# 2023-08-05_LVMi_Thermistors.net
KiCad netlist of a schematic drawn in EAGLE
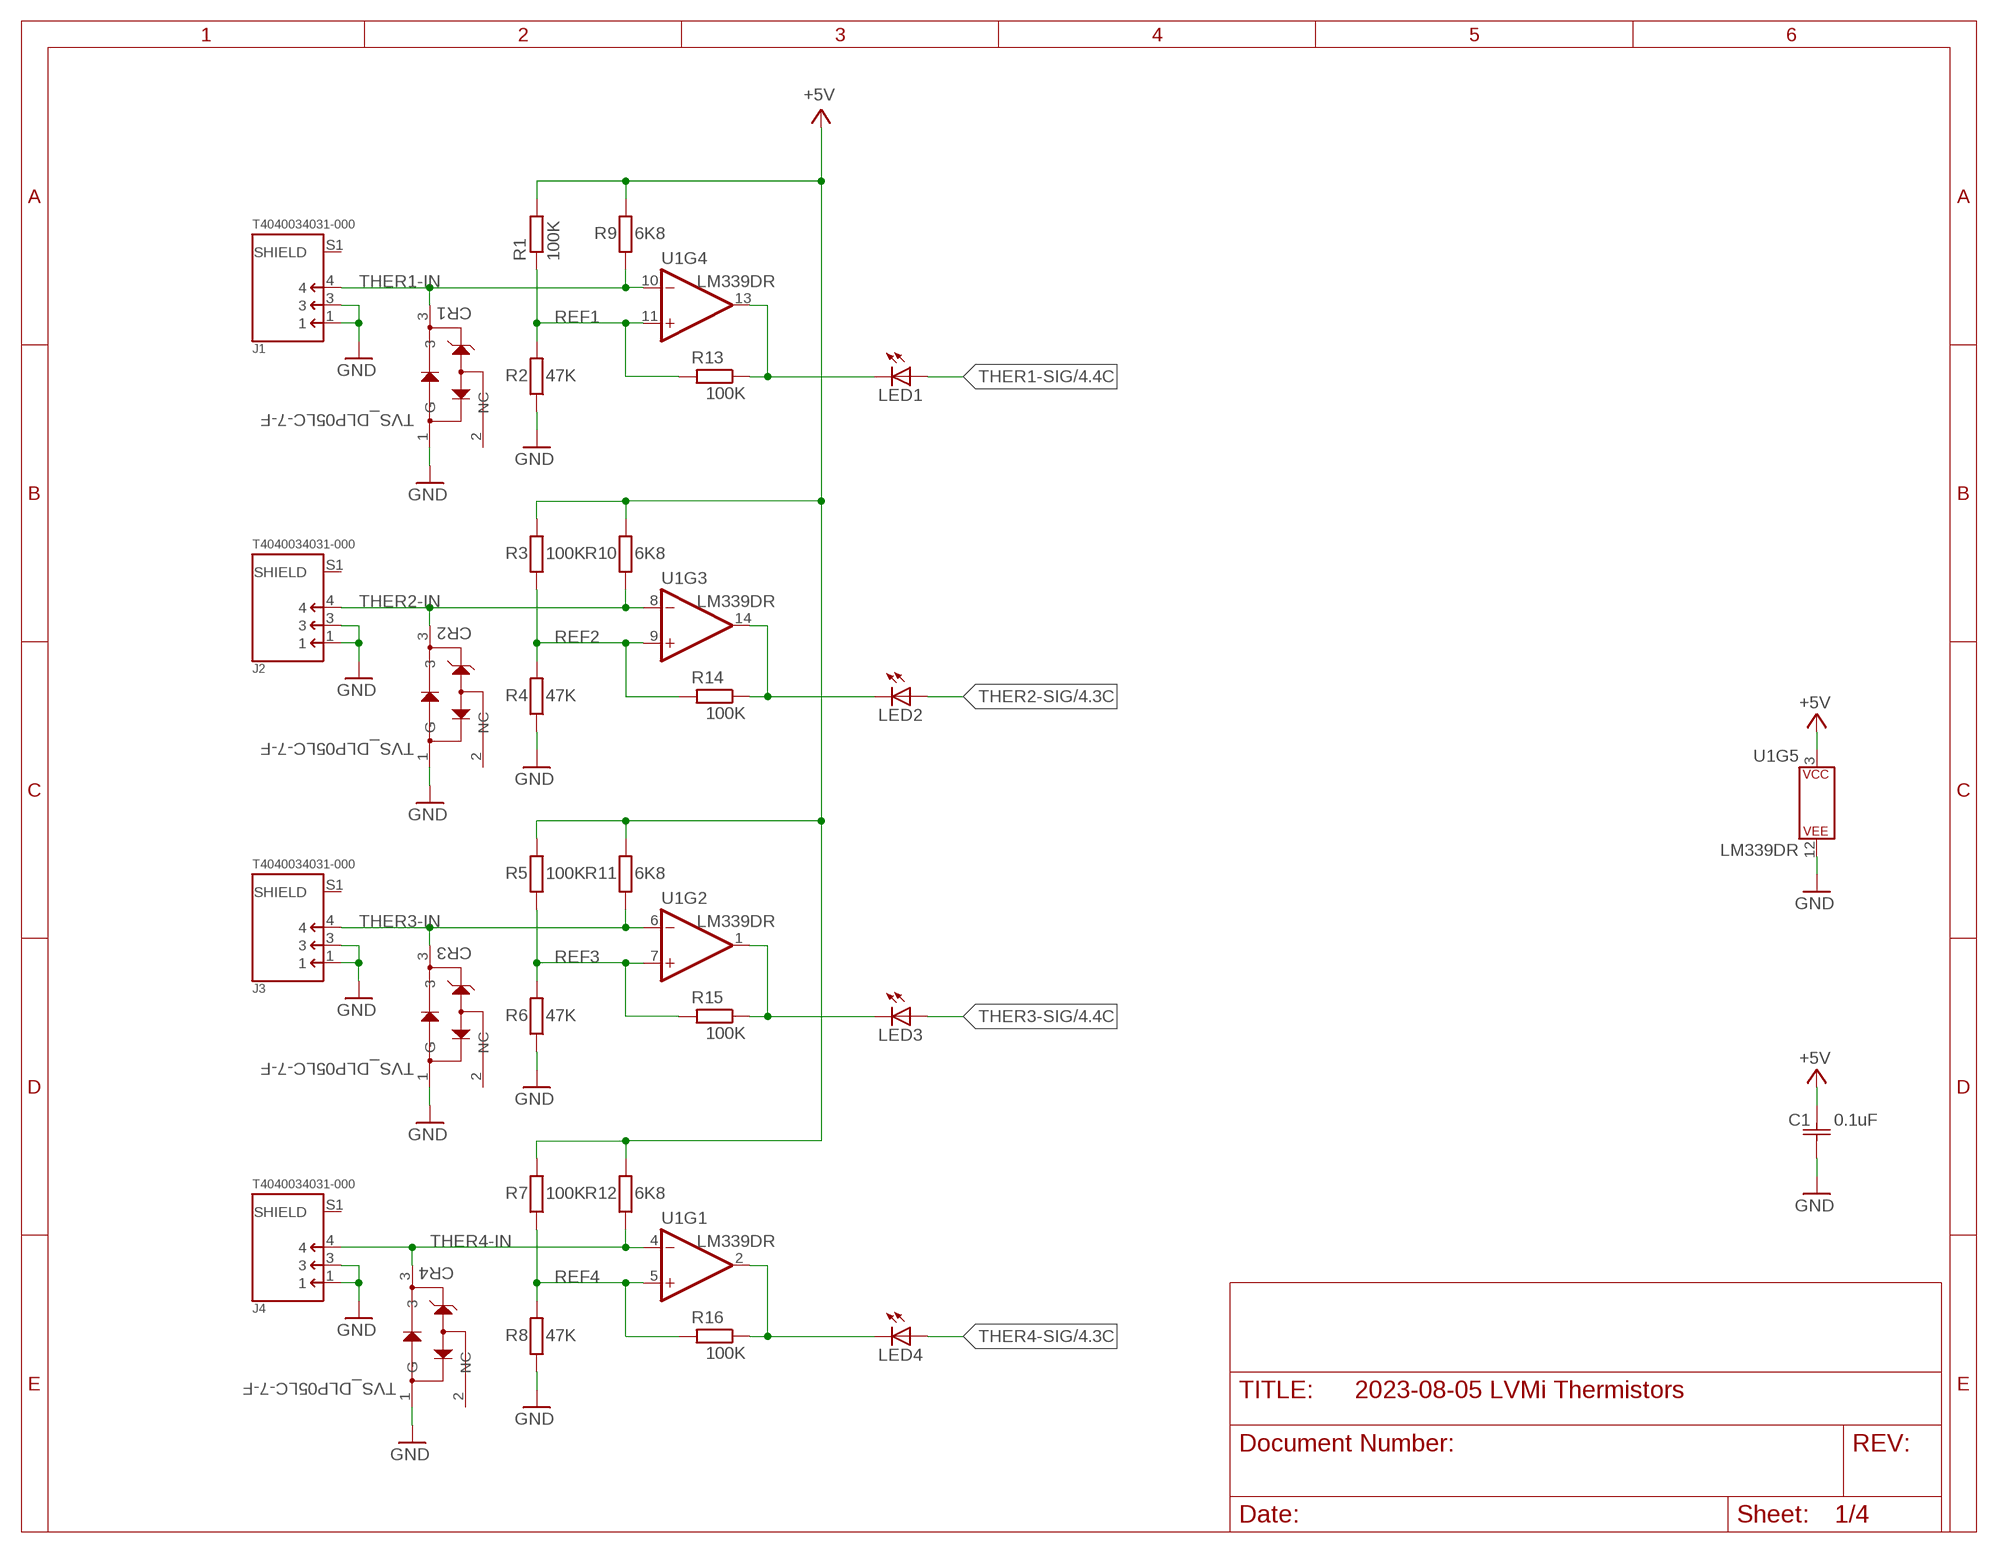
[diagram p0: schematic, sheet 1]
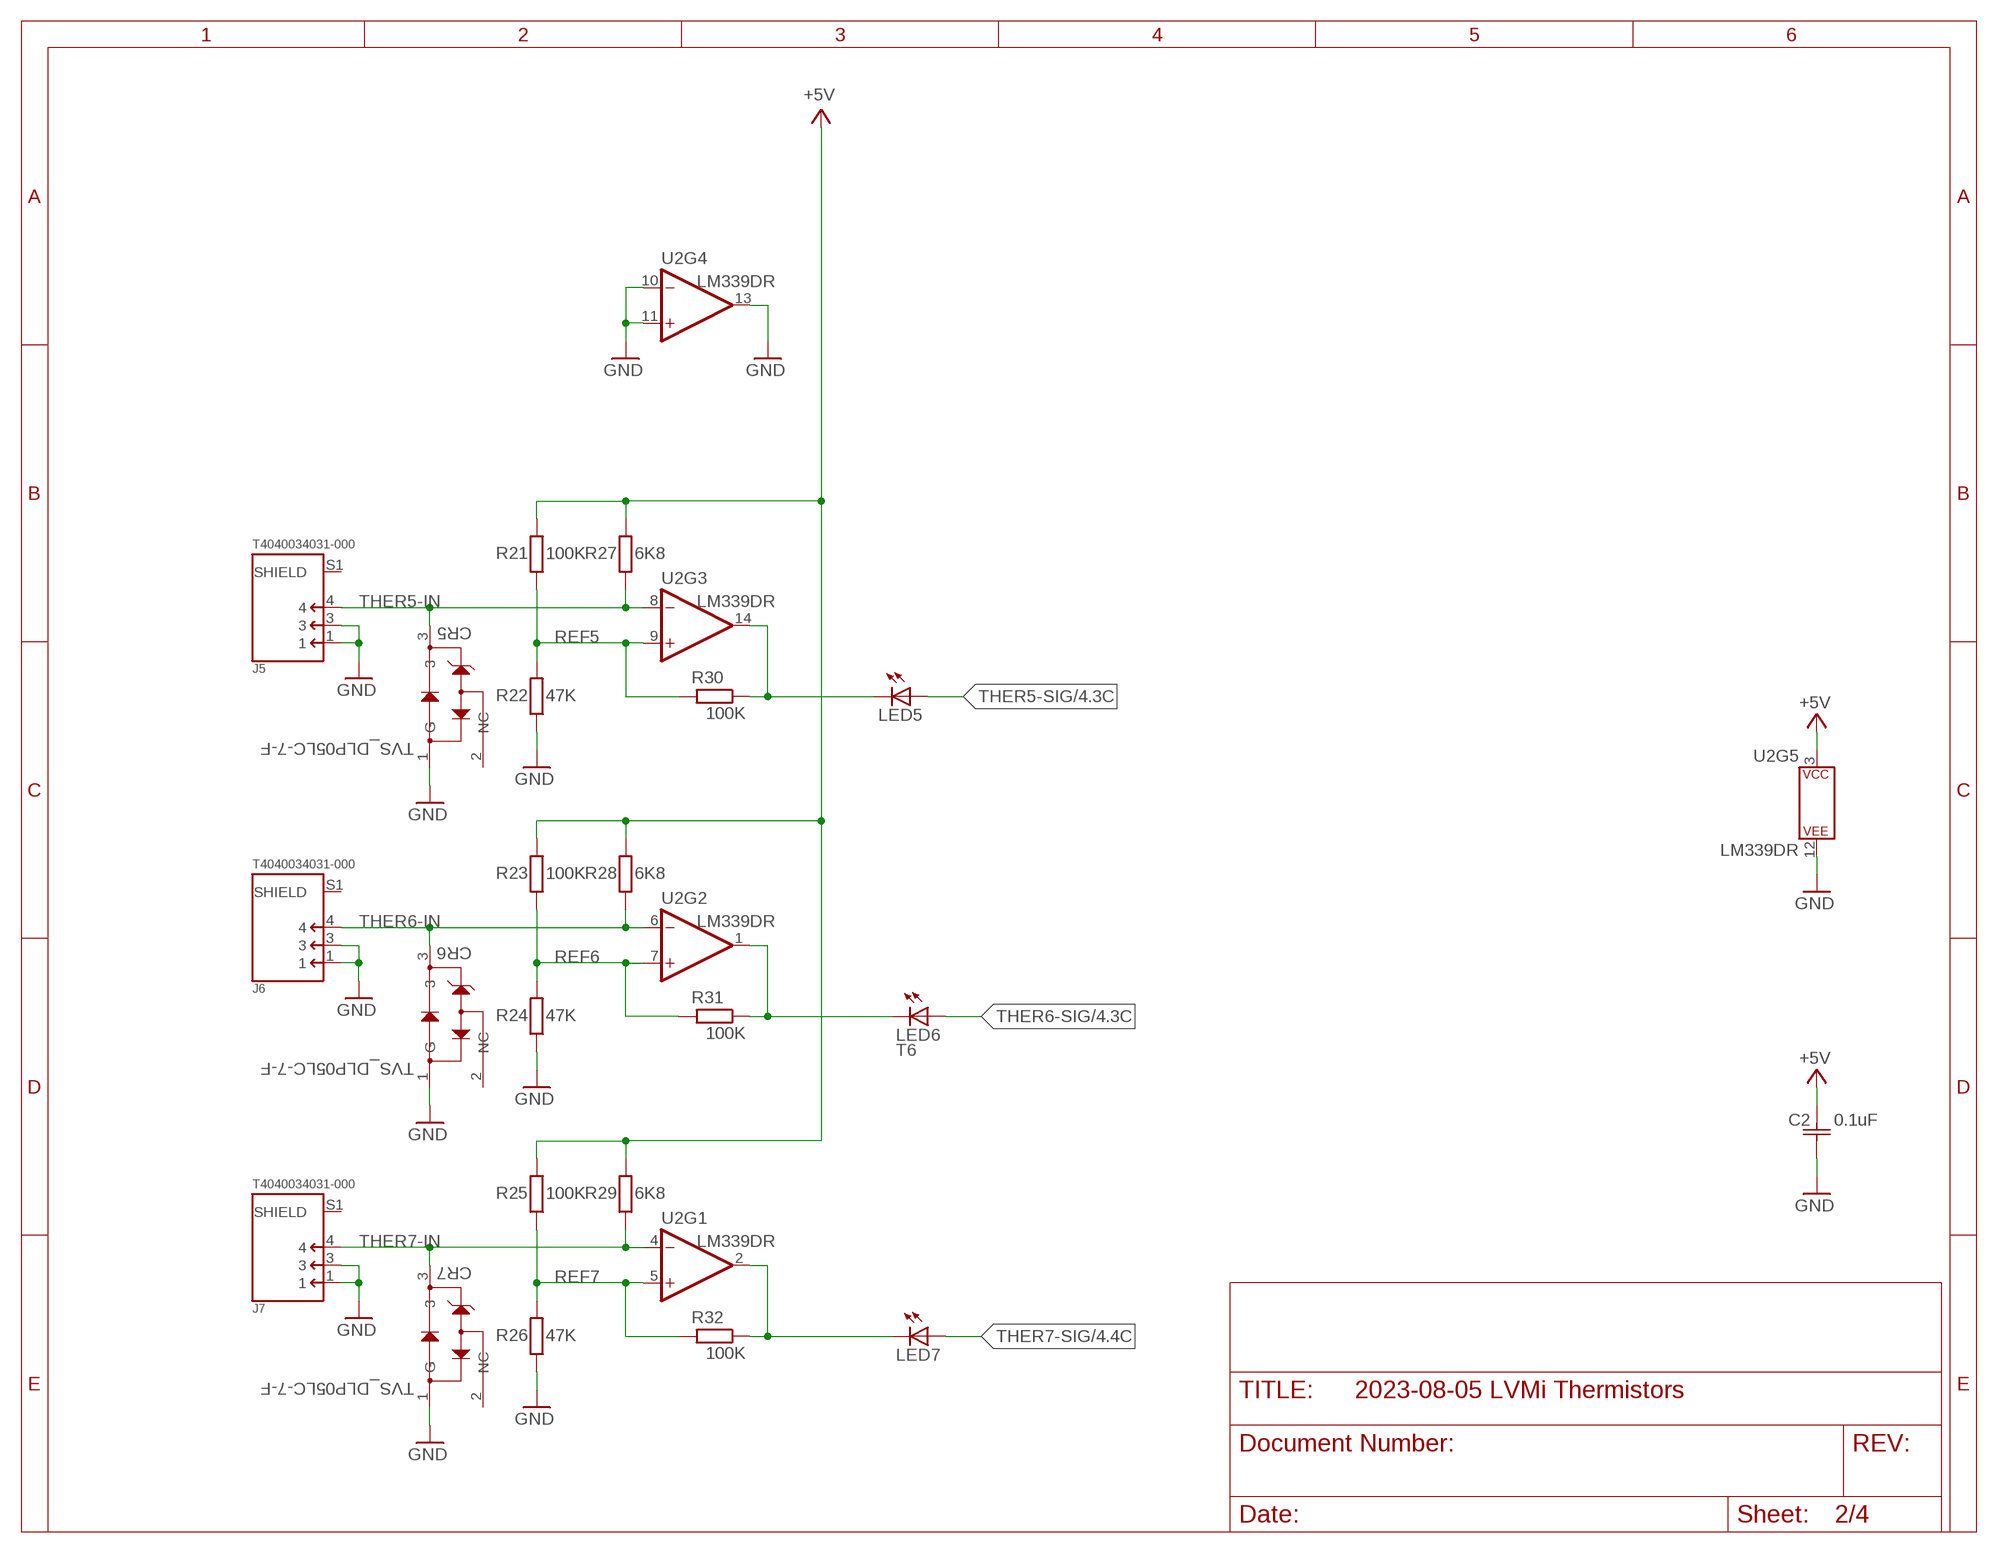
[diagram p1: schematic, sheet 2]
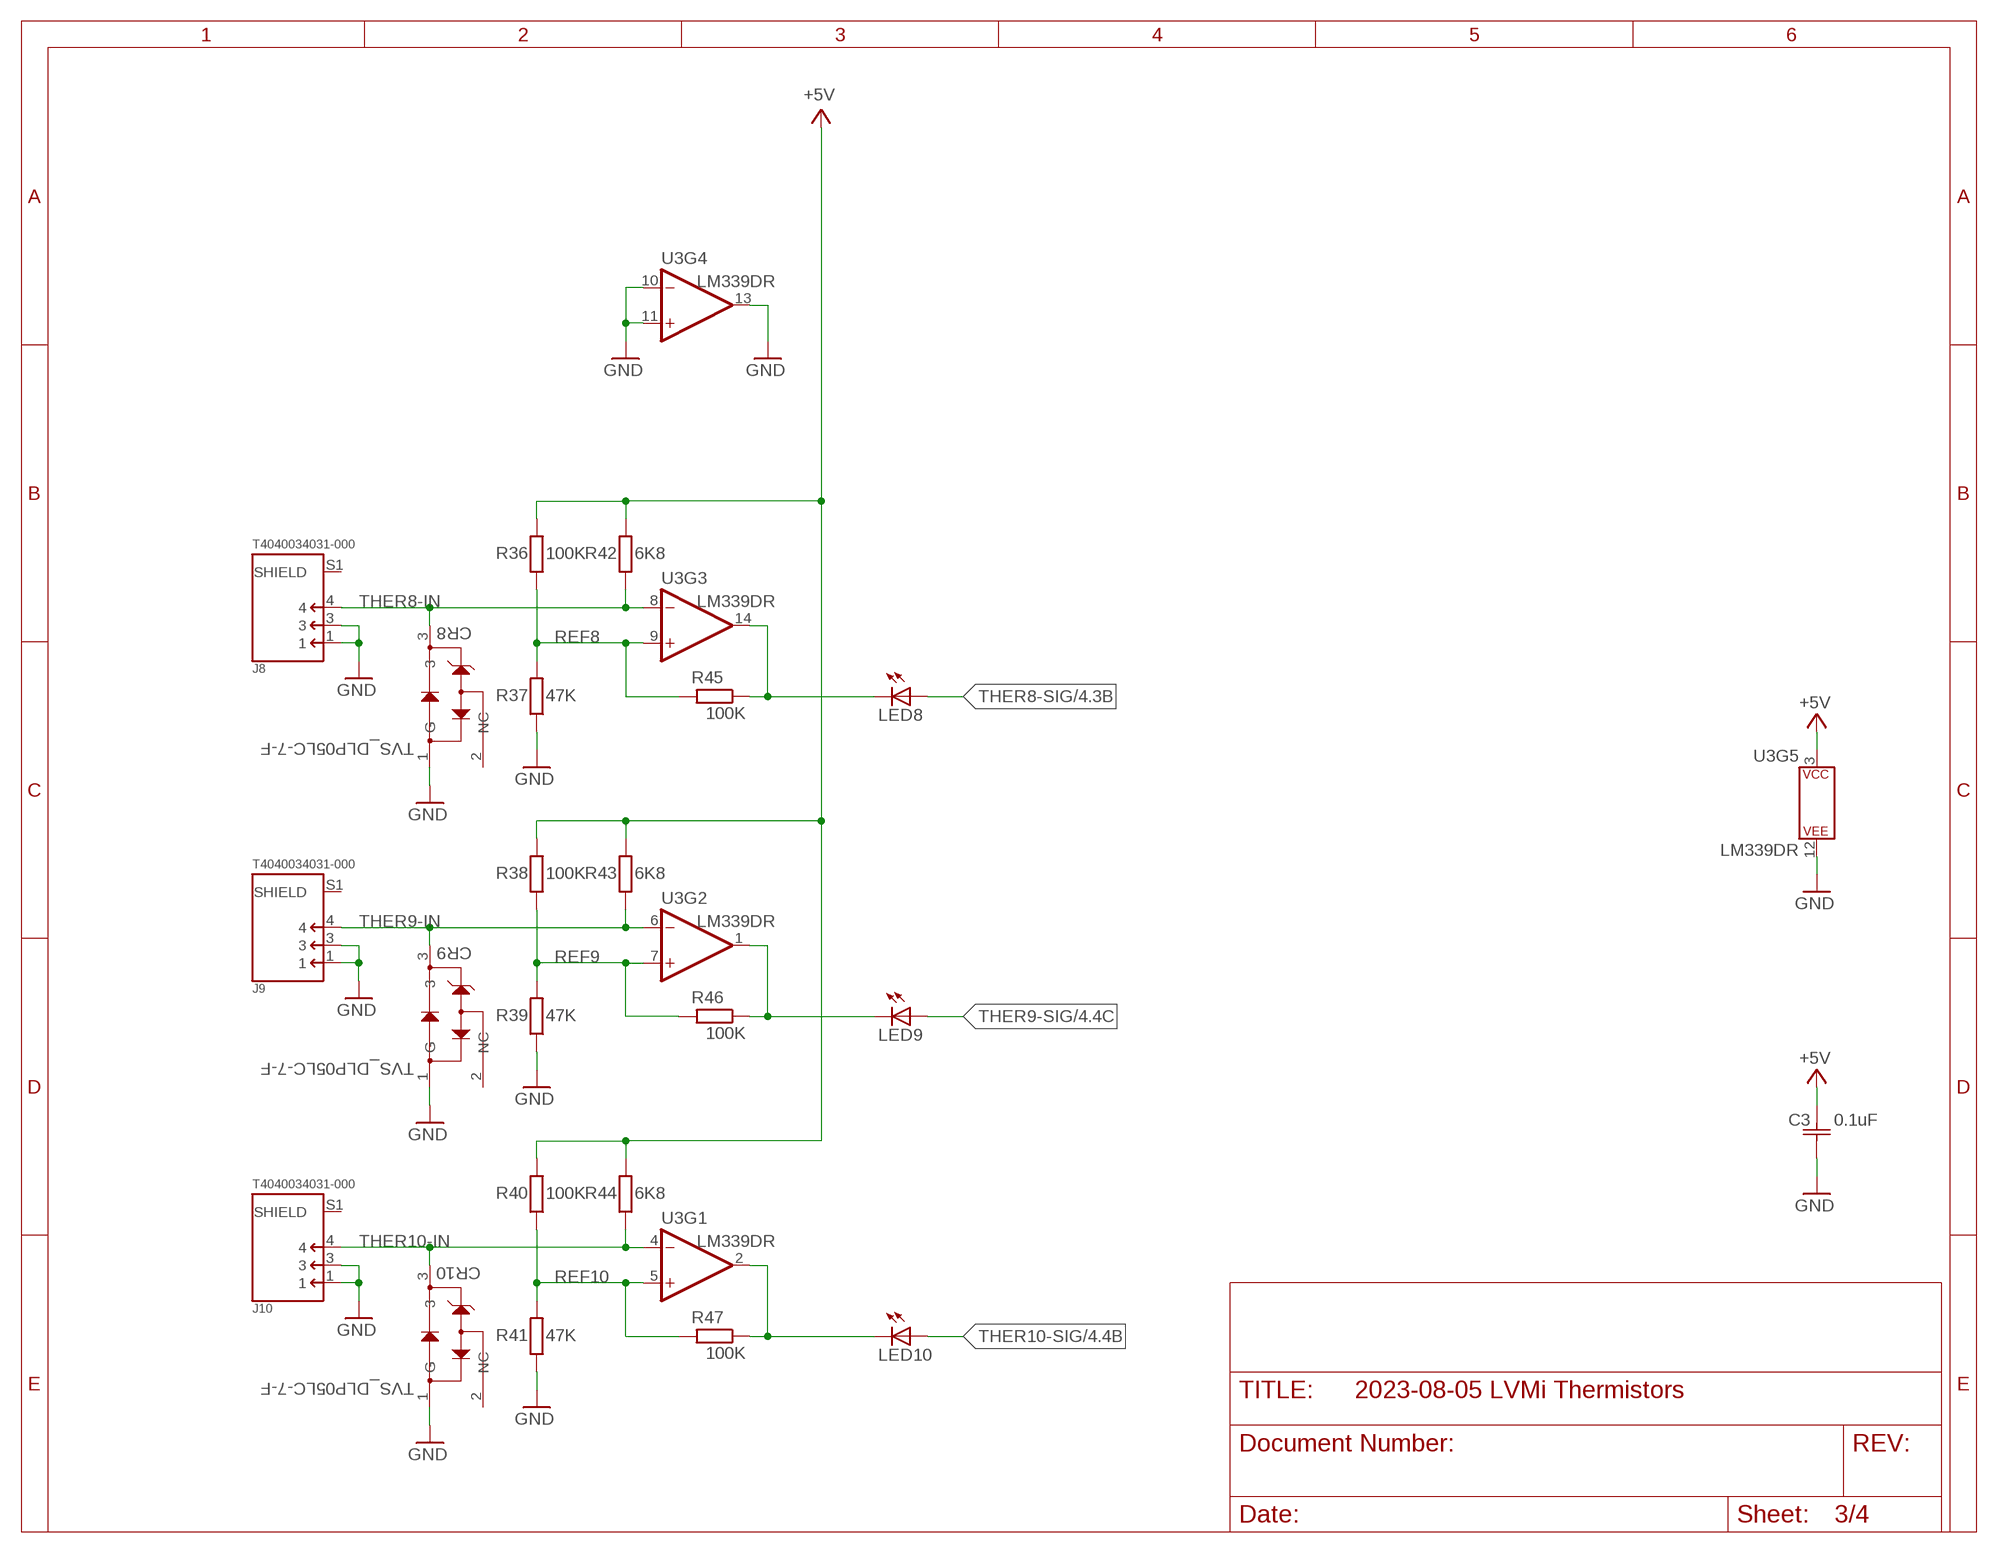
[diagram p2: schematic, sheet 3]
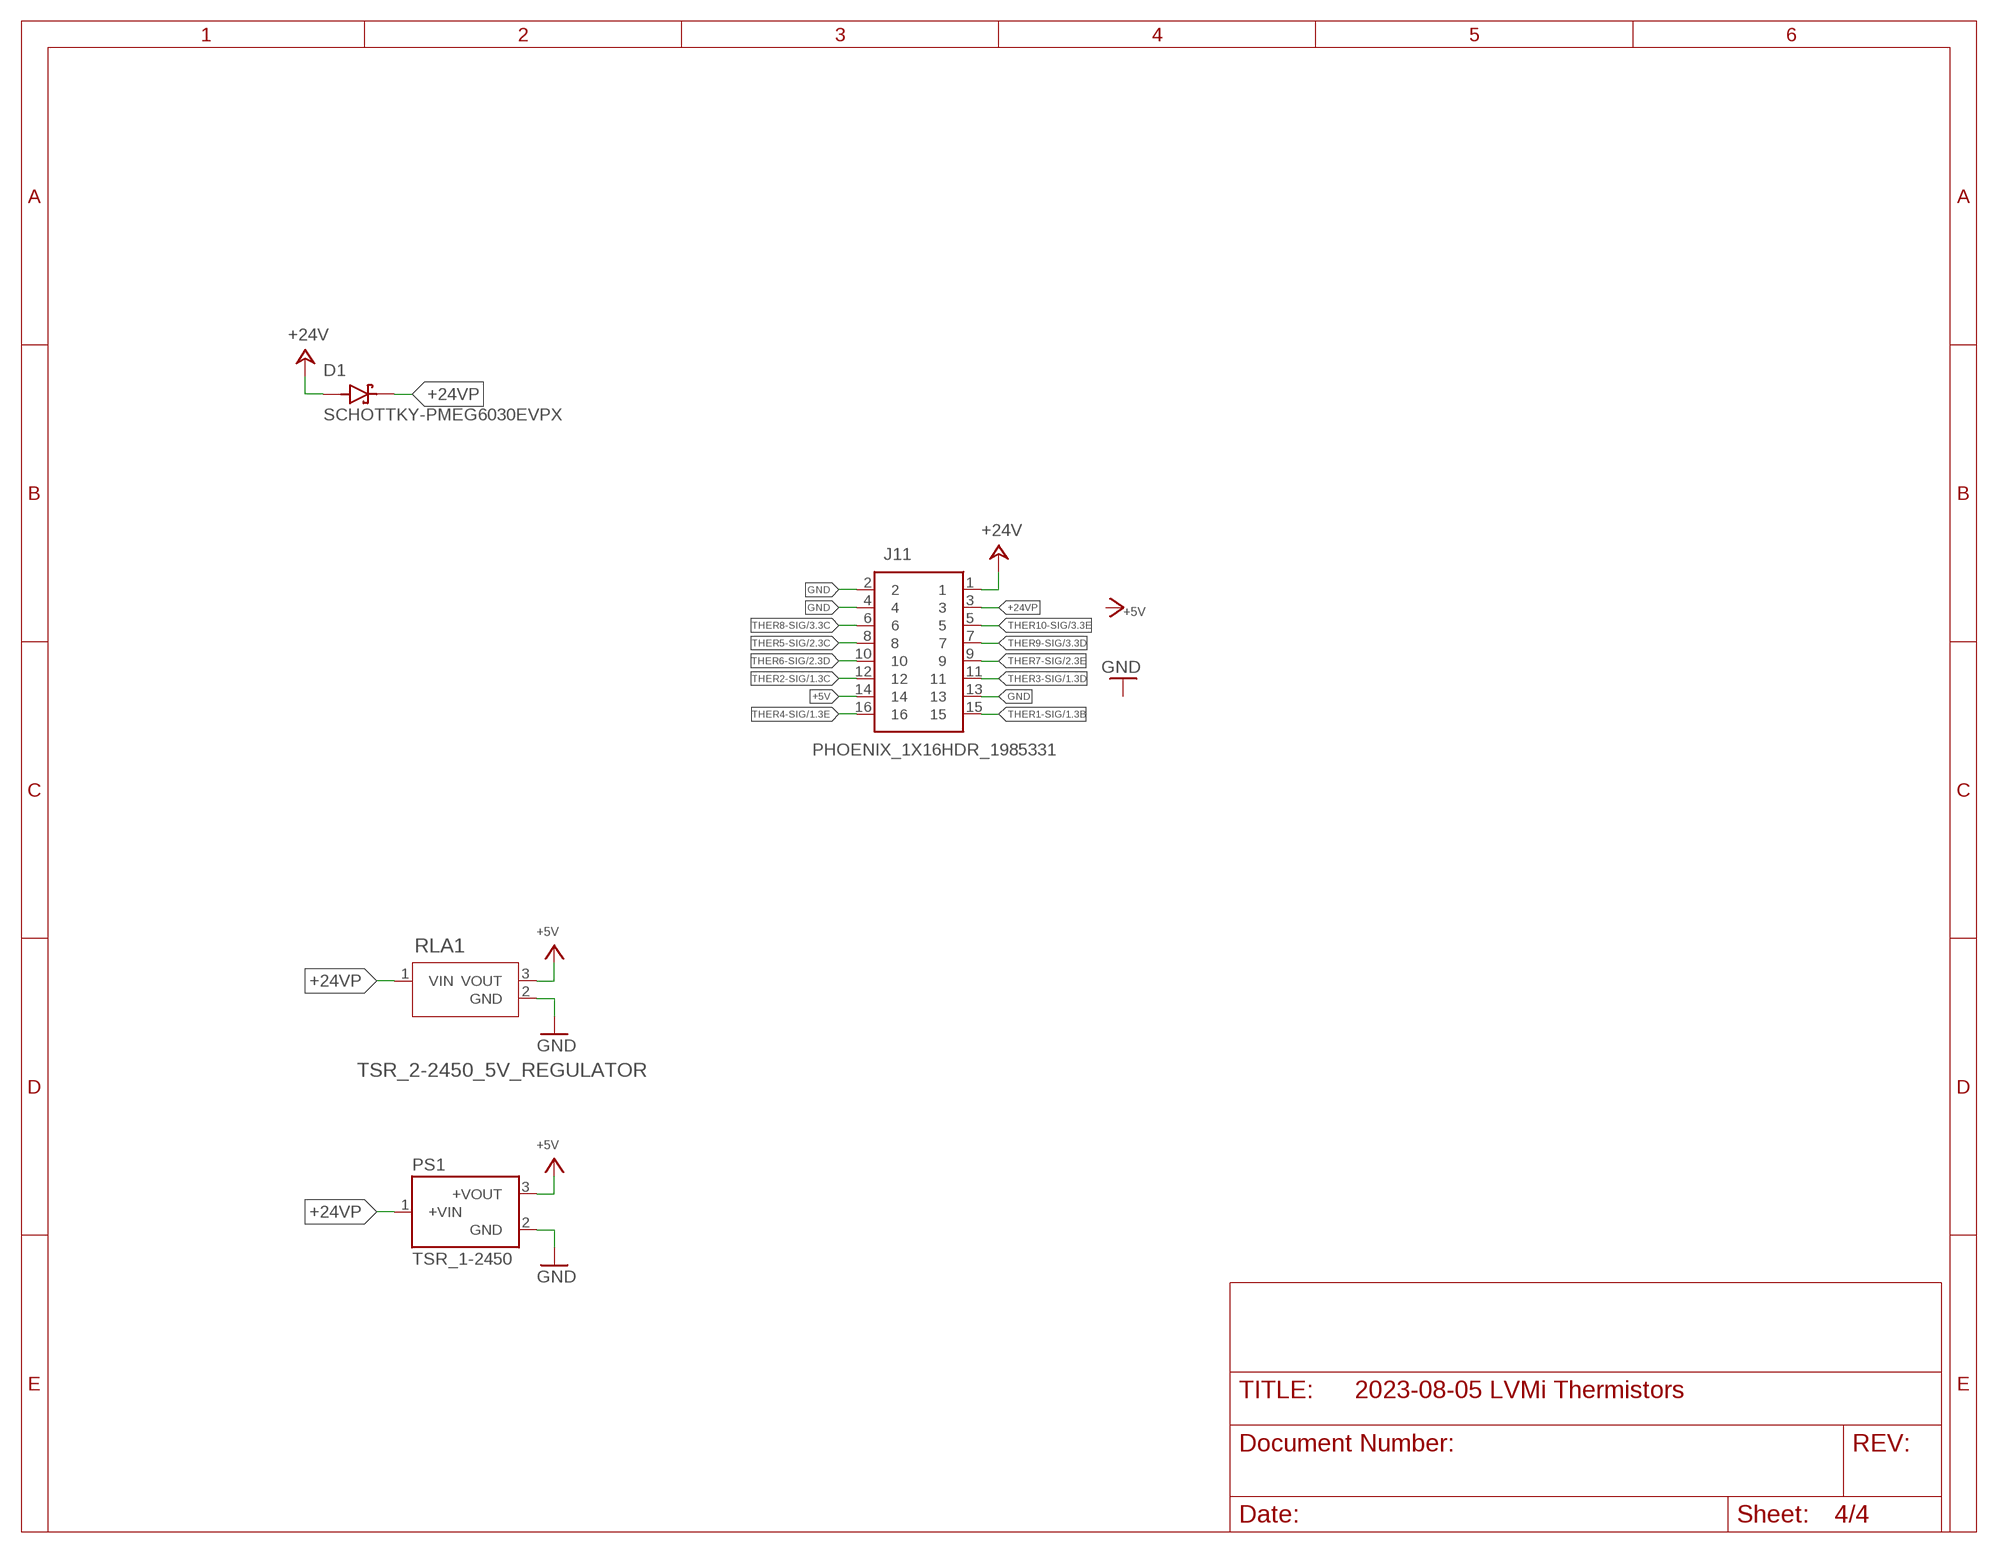
[diagram p3: schematic, sheet 4]

(export (version "E")
  (design (tool "Eeschema 10.0.6"))
  (components
    (comp (ref "C3")
      (value "0.1uF")
      (footprint "eagle-import:K104K15X7RF5TL2_VIS")
      (fields
        (field (name "MANUFACTURER_PART_NUMBER") "K104K15X7RF5TL2")
        (field (name "COPYRIGHT") "Copyright (C) 2023 Ultra Librarian. All rights reserved.")
      )
      (libsource (lib "eagle-import") (part "CAPTHRUHOLE"))
    )
    (comp (ref "CR8")
      (value "TVS_DLP05LC-7-F")
      (footprint "eagle-import:SOT23_DLP05LC_DIO")
      (fields
        (field (name "MANUFACTURER_PART_NUMBER") "DLP05LC-7-F")
        (field (name "COPYRIGHT") "Copyright (C) 2023 Ultra Librarian. All rights reserved.")
      )
      (libsource (lib "eagle-import") (part "TVS_DLP05LC-7-F"))
    )
    (comp (ref "CR9")
      (value "TVS_DLP05LC-7-F")
      (footprint "eagle-import:SOT23_DLP05LC_DIO")
      (fields
        (field (name "MANUFACTURER_PART_NUMBER") "DLP05LC-7-F")
        (field (name "COPYRIGHT") "Copyright (C) 2023 Ultra Librarian. All rights reserved.")
      )
      (libsource (lib "eagle-import") (part "TVS_DLP05LC-7-F"))
    )
    (comp (ref "CR10")
      (value "TVS_DLP05LC-7-F")
      (footprint "eagle-import:SOT23_DLP05LC_DIO")
      (fields
        (field (name "MANUFACTURER_PART_NUMBER") "DLP05LC-7-F")
        (field (name "COPYRIGHT") "Copyright (C) 2023 Ultra Librarian. All rights reserved.")
      )
      (libsource (lib "eagle-import") (part "TVS_DLP05LC-7-F"))
    )
    (comp (ref "J8")
      (value "T4040034031-000")
      (footprint "eagle-import:TE_T4040034031-000")
      (fields (field (name "MANUFACTURER") "TE "))
      (libsource (lib "eagle-import") (part "T4040034031-000"))
    )
    (comp (ref "J9")
      (value "T4040034031-000")
      (footprint "eagle-import:TE_T4040034031-000")
      (fields (field (name "MANUFACTURER") "TE "))
      (libsource (lib "eagle-import") (part "T4040034031-000"))
    )
    (comp (ref "J10")
      (value "T4040034031-000")
      (footprint "eagle-import:TE_T4040034031-000")
      (fields (field (name "MANUFACTURER") "TE "))
      (libsource (lib "eagle-import") (part "T4040034031-000"))
    )
    (comp (ref "LED8")
      (value "LED5MM")
      (footprint "eagle-import:LED5MM")
      (libsource (lib "eagle-import") (part "LED5MM"))
    )
    (comp (ref "LED9")
      (value "LED5MM")
      (footprint "eagle-import:LED5MM")
      (libsource (lib "eagle-import") (part "LED5MM"))
    )
    (comp (ref "LED10")
      (value "LED5MM")
      (footprint "eagle-import:LED5MM")
      (libsource (lib "eagle-import") (part "LED5MM"))
    )
    (comp (ref "R36")
      (value "100K")
      (footprint "eagle-import:0204_7")
      (libsource (lib "eagle-import") (part "R-EU_0204/7"))
    )
    (comp (ref "R37")
      (value "47K")
      (footprint "eagle-import:0204_7")
      (libsource (lib "eagle-import") (part "R-EU_0204/7"))
    )
    (comp (ref "R38")
      (value "100K")
      (footprint "eagle-import:0204_7")
      (libsource (lib "eagle-import") (part "R-EU_0204/7"))
    )
    (comp (ref "R39")
      (value "47K")
      (footprint "eagle-import:0204_7")
      (libsource (lib "eagle-import") (part "R-EU_0204/7"))
    )
    (comp (ref "R40")
      (value "100K")
      (footprint "eagle-import:0204_7")
      (libsource (lib "eagle-import") (part "R-EU_0204/7"))
    )
    (comp (ref "R41")
      (value "47K")
      (footprint "eagle-import:0204_7")
      (libsource (lib "eagle-import") (part "R-EU_0204/7"))
    )
    (comp (ref "R42")
      (value "6K8")
      (footprint "eagle-import:0204_7")
      (libsource (lib "eagle-import") (part "R-EU_0204/7"))
    )
    (comp (ref "R43")
      (value "6K8")
      (footprint "eagle-import:0204_7")
      (libsource (lib "eagle-import") (part "R-EU_0204/7"))
    )
    (comp (ref "R44")
      (value "6K8")
      (footprint "eagle-import:0204_7")
      (libsource (lib "eagle-import") (part "R-EU_0204/7"))
    )
    (comp (ref "R45")
      (value "100K")
      (footprint "eagle-import:0204_7")
      (libsource (lib "eagle-import") (part "R-EU_0204/7"))
    )
    (comp (ref "R46")
      (value "100K")
      (footprint "eagle-import:0204_7")
      (libsource (lib "eagle-import") (part "R-EU_0204/7"))
    )
    (comp (ref "R47")
      (value "100K")
      (footprint "eagle-import:0204_7")
      (libsource (lib "eagle-import") (part "R-EU_0204/7"))
    )
    (comp (ref "U3")
      (value "LM339DR")
      (footprint "eagle-import:SOIC127P599X175-14")
      (libsource (lib "eagle-import") (part "LM339SOIC-14"))
    )
    (comp (ref "D1")
      (value "SCHOTTKY-PMEG6030EVPX")
      (footprint "eagle-import:DIO_PMEG6030EVPX")
      (fields
        (field (name "DIGI-KEY_PART_NUMBER") "1727-1349-1-ND")
        (field (name "MF") "Nexperia USA")
        (field (name "MP") "PMEG6030EVPX")
      )
      (libsource (lib "eagle-import") (part "SCHOTTKY-PMEG6030EVPX"))
    )
    (comp (ref "J11")
      (value "PHOENIX_1X16HDR_1985331")
      (footprint "eagle-import:1985331")
      (fields
        (field (name "MANUFACTURER_PART_NUMBER") "1985331")
        (field (name "MOUSER_PART_NUMBER") "651-1985331")
      )
      (libsource (lib "eagle-import") (part "PHOENIX_1X16HDR_1985331"))
    )
    (comp (ref "PS1")
      (value "TSR_1-2450")
      (footprint "eagle-import:CONV_TSR_1-2450")
      (fields (field (name "MANUFACTURER") "Traco Power"))
      (libsource (lib "eagle-import") (part "TSR_1-2450"))
    )
    (comp (ref "RLA1")
      (value "TSR_2-2450_5V_REGULATOR")
      (footprint "eagle-import:TSR2-SINGLE_TRP")
      (fields
        (field (name "MANUFACTURER_PART_NUMBER") "TSR 2-2450")
        (field (name "COPYRIGHT") "Copyright (C) 2022 Ultra Librarian. All rights reserved.")
      )
      (libsource (lib "eagle-import") (part "TSR_2-2450_5V_REGULATOR"))
    )
    (comp (ref "C2")
      (value "0.1uF")
      (footprint "eagle-import:K104K15X7RF5TL2_VIS")
      (fields
        (field (name "MANUFACTURER_PART_NUMBER") "K104K15X7RF5TL2")
        (field (name "COPYRIGHT") "Copyright (C) 2023 Ultra Librarian. All rights reserved.")
      )
      (libsource (lib "eagle-import") (part "CAPTHRUHOLE"))
    )
    (comp (ref "CR5")
      (value "TVS_DLP05LC-7-F")
      (footprint "eagle-import:SOT23_DLP05LC_DIO")
      (fields
        (field (name "MANUFACTURER_PART_NUMBER") "DLP05LC-7-F")
        (field (name "COPYRIGHT") "Copyright (C) 2023 Ultra Librarian. All rights reserved.")
      )
      (libsource (lib "eagle-import") (part "TVS_DLP05LC-7-F"))
    )
    (comp (ref "CR6")
      (value "TVS_DLP05LC-7-F")
      (footprint "eagle-import:SOT23_DLP05LC_DIO")
      (fields
        (field (name "MANUFACTURER_PART_NUMBER") "DLP05LC-7-F")
        (field (name "COPYRIGHT") "Copyright (C) 2023 Ultra Librarian. All rights reserved.")
      )
      (libsource (lib "eagle-import") (part "TVS_DLP05LC-7-F"))
    )
    (comp (ref "CR7")
      (value "TVS_DLP05LC-7-F")
      (footprint "eagle-import:SOT23_DLP05LC_DIO")
      (fields
        (field (name "MANUFACTURER_PART_NUMBER") "DLP05LC-7-F")
        (field (name "COPYRIGHT") "Copyright (C) 2023 Ultra Librarian. All rights reserved.")
      )
      (libsource (lib "eagle-import") (part "TVS_DLP05LC-7-F"))
    )
    (comp (ref "J5")
      (value "T4040034031-000")
      (footprint "eagle-import:TE_T4040034031-000")
      (fields (field (name "MANUFACTURER") "TE "))
      (libsource (lib "eagle-import") (part "T4040034031-000"))
    )
    (comp (ref "J6")
      (value "T4040034031-000")
      (footprint "eagle-import:TE_T4040034031-000")
      (fields (field (name "MANUFACTURER") "TE "))
      (libsource (lib "eagle-import") (part "T4040034031-000"))
    )
    (comp (ref "J7")
      (value "T4040034031-000")
      (footprint "eagle-import:TE_T4040034031-000")
      (fields (field (name "MANUFACTURER") "TE "))
      (libsource (lib "eagle-import") (part "T4040034031-000"))
    )
    (comp (ref "LED5")
      (value "LED5MM")
      (footprint "eagle-import:LED5MM")
      (libsource (lib "eagle-import") (part "LED5MM"))
    )
    (comp (ref "LED6")
      (value "T6")
      (footprint "eagle-import:LED5MM")
      (libsource (lib "eagle-import") (part "LED5MM"))
    )
    (comp (ref "LED7")
      (value "LED5MM")
      (footprint "eagle-import:LED5MM")
      (libsource (lib "eagle-import") (part "LED5MM"))
    )
    (comp (ref "R21")
      (value "100K")
      (footprint "eagle-import:0204_7")
      (libsource (lib "eagle-import") (part "R-EU_0204/7"))
    )
    (comp (ref "R22")
      (value "47K")
      (footprint "eagle-import:0204_7")
      (libsource (lib "eagle-import") (part "R-EU_0204/7"))
    )
    (comp (ref "R23")
      (value "100K")
      (footprint "eagle-import:0204_7")
      (libsource (lib "eagle-import") (part "R-EU_0204/7"))
    )
    (comp (ref "R24")
      (value "47K")
      (footprint "eagle-import:0204_7")
      (libsource (lib "eagle-import") (part "R-EU_0204/7"))
    )
    (comp (ref "R25")
      (value "100K")
      (footprint "eagle-import:0204_7")
      (libsource (lib "eagle-import") (part "R-EU_0204/7"))
    )
    (comp (ref "R26")
      (value "47K")
      (footprint "eagle-import:0204_7")
      (libsource (lib "eagle-import") (part "R-EU_0204/7"))
    )
    (comp (ref "R27")
      (value "6K8")
      (footprint "eagle-import:0204_7")
      (libsource (lib "eagle-import") (part "R-EU_0204/7"))
    )
    (comp (ref "R28")
      (value "6K8")
      (footprint "eagle-import:0204_7")
      (libsource (lib "eagle-import") (part "R-EU_0204/7"))
    )
    (comp (ref "R29")
      (value "6K8")
      (footprint "eagle-import:0204_7")
      (libsource (lib "eagle-import") (part "R-EU_0204/7"))
    )
    (comp (ref "R30")
      (value "100K")
      (footprint "eagle-import:0204_7")
      (libsource (lib "eagle-import") (part "R-EU_0204/7"))
    )
    (comp (ref "R31")
      (value "100K")
      (footprint "eagle-import:0204_7")
      (libsource (lib "eagle-import") (part "R-EU_0204/7"))
    )
    (comp (ref "R32")
      (value "100K")
      (footprint "eagle-import:0204_7")
      (libsource (lib "eagle-import") (part "R-EU_0204/7"))
    )
    (comp (ref "U2")
      (value "LM339DR")
      (footprint "eagle-import:SOIC127P599X175-14")
      (libsource (lib "eagle-import") (part "LM339SOIC-14"))
    )
    (comp (ref "C1")
      (value "0.1uF")
      (footprint "eagle-import:K104K15X7RF5TL2_VIS")
      (fields
        (field (name "MANUFACTURER_PART_NUMBER") "K104K15X7RF5TL2")
        (field (name "COPYRIGHT") "Copyright (C) 2023 Ultra Librarian. All rights reserved.")
      )
      (libsource (lib "eagle-import") (part "CAPTHRUHOLE"))
    )
    (comp (ref "CR1")
      (value "TVS_DLP05LC-7-F")
      (footprint "eagle-import:SOT23_DLP05LC_DIO")
      (fields
        (field (name "MANUFACTURER_PART_NUMBER") "DLP05LC-7-F")
        (field (name "COPYRIGHT") "Copyright (C) 2023 Ultra Librarian. All rights reserved.")
      )
      (libsource (lib "eagle-import") (part "TVS_DLP05LC-7-F"))
    )
    (comp (ref "CR2")
      (value "TVS_DLP05LC-7-F")
      (footprint "eagle-import:SOT23_DLP05LC_DIO")
      (fields
        (field (name "MANUFACTURER_PART_NUMBER") "DLP05LC-7-F")
        (field (name "COPYRIGHT") "Copyright (C) 2023 Ultra Librarian. All rights reserved.")
      )
      (libsource (lib "eagle-import") (part "TVS_DLP05LC-7-F"))
    )
    (comp (ref "CR3")
      (value "TVS_DLP05LC-7-F")
      (footprint "eagle-import:SOT23_DLP05LC_DIO")
      (fields
        (field (name "MANUFACTURER_PART_NUMBER") "DLP05LC-7-F")
        (field (name "COPYRIGHT") "Copyright (C) 2023 Ultra Librarian. All rights reserved.")
      )
      (libsource (lib "eagle-import") (part "TVS_DLP05LC-7-F"))
    )
    (comp (ref "CR4")
      (value "TVS_DLP05LC-7-F")
      (footprint "eagle-import:SOT23_DLP05LC_DIO")
      (fields
        (field (name "MANUFACTURER_PART_NUMBER") "DLP05LC-7-F")
        (field (name "COPYRIGHT") "Copyright (C) 2023 Ultra Librarian. All rights reserved.")
      )
      (libsource (lib "eagle-import") (part "TVS_DLP05LC-7-F"))
    )
    (comp (ref "J1")
      (value "T4040034031-000")
      (footprint "eagle-import:TE_T4040034031-000")
      (fields (field (name "MANUFACTURER") "TE "))
      (libsource (lib "eagle-import") (part "T4040034031-000"))
    )
    (comp (ref "J2")
      (value "T4040034031-000")
      (footprint "eagle-import:TE_T4040034031-000")
      (fields (field (name "MANUFACTURER") "TE "))
      (libsource (lib "eagle-import") (part "T4040034031-000"))
    )
    (comp (ref "J3")
      (value "T4040034031-000")
      (footprint "eagle-import:TE_T4040034031-000")
      (fields (field (name "MANUFACTURER") "TE "))
      (libsource (lib "eagle-import") (part "T4040034031-000"))
    )
    (comp (ref "J4")
      (value "T4040034031-000")
      (footprint "eagle-import:TE_T4040034031-000")
      (fields (field (name "MANUFACTURER") "TE "))
      (libsource (lib "eagle-import") (part "T4040034031-000"))
    )
    (comp (ref "LED1")
      (value "LED5MM")
      (footprint "eagle-import:LED5MM")
      (libsource (lib "eagle-import") (part "LED5MM"))
    )
    (comp (ref "LED2")
      (value "LED5MM")
      (footprint "eagle-import:LED5MM")
      (libsource (lib "eagle-import") (part "LED5MM"))
    )
    (comp (ref "LED3")
      (value "LED5MM")
      (footprint "eagle-import:LED5MM")
      (libsource (lib "eagle-import") (part "LED5MM"))
    )
    (comp (ref "LED4")
      (value "LED5MM")
      (footprint "eagle-import:LED5MM")
      (libsource (lib "eagle-import") (part "LED5MM"))
    )
    (comp (ref "R1")
      (value "100K")
      (footprint "eagle-import:0204_7")
      (libsource (lib "eagle-import") (part "R-EU_0204/7"))
    )
    (comp (ref "R2")
      (value "47K")
      (footprint "eagle-import:0204_7")
      (libsource (lib "eagle-import") (part "R-EU_0204/7"))
    )
    (comp (ref "R3")
      (value "100K")
      (footprint "eagle-import:0204_7")
      (libsource (lib "eagle-import") (part "R-EU_0204/7"))
    )
    (comp (ref "R4")
      (value "47K")
      (footprint "eagle-import:0204_7")
      (libsource (lib "eagle-import") (part "R-EU_0204/7"))
    )
    (comp (ref "R5")
      (value "100K")
      (footprint "eagle-import:0204_7")
      (libsource (lib "eagle-import") (part "R-EU_0204/7"))
    )
    (comp (ref "R6")
      (value "47K")
      (footprint "eagle-import:0204_7")
      (libsource (lib "eagle-import") (part "R-EU_0204/7"))
    )
    (comp (ref "R7")
      (value "100K")
      (footprint "eagle-import:0204_7")
      (libsource (lib "eagle-import") (part "R-EU_0204/7"))
    )
    (comp (ref "R8")
      (value "47K")
      (footprint "eagle-import:0204_7")
      (libsource (lib "eagle-import") (part "R-EU_0204/7"))
    )
    (comp (ref "R9")
      (value "6K8")
      (footprint "eagle-import:0204_7")
      (libsource (lib "eagle-import") (part "R-EU_0204/7"))
    )
    (comp (ref "R10")
      (value "6K8")
      (footprint "eagle-import:0204_7")
      (libsource (lib "eagle-import") (part "R-EU_0204/7"))
    )
    (comp (ref "R11")
      (value "6K8")
      (footprint "eagle-import:0204_7")
      (libsource (lib "eagle-import") (part "R-EU_0204/7"))
    )
    (comp (ref "R12")
      (value "6K8")
      (footprint "eagle-import:0204_7")
      (libsource (lib "eagle-import") (part "R-EU_0204/7"))
    )
    (comp (ref "R13")
      (value "100K")
      (footprint "eagle-import:0204_7")
      (libsource (lib "eagle-import") (part "R-EU_0204/7"))
    )
    (comp (ref "R14")
      (value "100K")
      (footprint "eagle-import:0204_7")
      (libsource (lib "eagle-import") (part "R-EU_0204/7"))
    )
    (comp (ref "R15")
      (value "100K")
      (footprint "eagle-import:0204_7")
      (libsource (lib "eagle-import") (part "R-EU_0204/7"))
    )
    (comp (ref "R16")
      (value "100K")
      (footprint "eagle-import:0204_7")
      (libsource (lib "eagle-import") (part "R-EU_0204/7"))
    )
    (comp (ref "U1")
      (value "LM339DR")
      (footprint "eagle-import:SOIC127P599X175-14")
      (libsource (lib "eagle-import") (part "LM339SOIC-14"))
    )
  )
  (nets
    (net (code "1") (name "+5V") (class "Default")
      (node (ref "C1") (pin "2") (pinfunction "2_2") (pintype "passive"))
      (node (ref "C2") (pin "2") (pinfunction "2_2") (pintype "passive"))
      (node (ref "C3") (pin "2") (pinfunction "2_2") (pintype "passive"))
      (node (ref "J11") (pin "14") (pinfunction "14_14") (pintype "bidirectional"))
      (node (ref "PS1") (pin "3") (pinfunction "+VOUT_3") (pintype "output"))
      (node (ref "R1") (pin "2") (pinfunction "2_2") (pintype "passive"))
      (node (ref "R10") (pin "2") (pinfunction "2_2") (pintype "passive"))
      (node (ref "R11") (pin "2") (pinfunction "2_2") (pintype "passive"))
      (node (ref "R12") (pin "2") (pinfunction "2_2") (pintype "passive"))
      (node (ref "R21") (pin "2") (pinfunction "2_2") (pintype "passive"))
      (node (ref "R23") (pin "2") (pinfunction "2_2") (pintype "passive"))
      (node (ref "R25") (pin "2") (pinfunction "2_2") (pintype "passive"))
      (node (ref "R27") (pin "2") (pinfunction "2_2") (pintype "passive"))
      (node (ref "R28") (pin "2") (pinfunction "2_2") (pintype "passive"))
      (node (ref "R29") (pin "2") (pinfunction "2_2") (pintype "passive"))
      (node (ref "R3") (pin "2") (pinfunction "2_2") (pintype "passive"))
      (node (ref "R36") (pin "2") (pinfunction "2_2") (pintype "passive"))
      (node (ref "R38") (pin "2") (pinfunction "2_2") (pintype "passive"))
      (node (ref "R40") (pin "2") (pinfunction "2_2") (pintype "passive"))
      (node (ref "R42") (pin "2") (pinfunction "2_2") (pintype "passive"))
      (node (ref "R43") (pin "2") (pinfunction "2_2") (pintype "passive"))
      (node (ref "R44") (pin "2") (pinfunction "2_2") (pintype "passive"))
      (node (ref "R5") (pin "2") (pinfunction "2_2") (pintype "passive"))
      (node (ref "R7") (pin "2") (pinfunction "2_2") (pintype "passive"))
      (node (ref "R9") (pin "2") (pinfunction "2_2") (pintype "passive"))
      (node (ref "RLA1") (pin "3") (pinfunction "VOUT_3") (pintype "passive"))
      (node (ref "U1") (pin "3") (pinfunction "P$V+_3") (pintype "bidirectional"))
      (node (ref "U2") (pin "3") (pinfunction "P$V+_3") (pintype "bidirectional"))
      (node (ref "U3") (pin "3") (pinfunction "P$V+_3") (pintype "bidirectional"))
    )
    (net (code "2") (name "+24V") (class "Default")
      (node (ref "D1") (pin "2") (pinfunction "A_2") (pintype "passive"))
      (node (ref "J11") (pin "1") (pinfunction "1_1") (pintype "bidirectional"))
    )
    (net (code "3") (name "+24VP") (class "Default")
      (node (ref "D1") (pin "1") (pinfunction "K_1") (pintype "passive"))
      (node (ref "J11") (pin "3") (pinfunction "3_3") (pintype "bidirectional"))
      (node (ref "PS1") (pin "1") (pinfunction "+VIN_1") (pintype "input"))
      (node (ref "RLA1") (pin "1") (pinfunction "VIN_1") (pintype "passive"))
    )
    (net (code "4") (name "GND") (class "Default")
      (node (ref "C1") (pin "1") (pinfunction "1_1") (pintype "passive"))
      (node (ref "C2") (pin "1") (pinfunction "1_1") (pintype "passive"))
      (node (ref "C3") (pin "1") (pinfunction "1_1") (pintype "passive"))
      (node (ref "CR1") (pin "1") (pinfunction "G_1") (pintype "passive"))
      (node (ref "CR10") (pin "1") (pinfunction "G_1") (pintype "passive"))
      (node (ref "CR2") (pin "1") (pinfunction "G_1") (pintype "passive"))
      (node (ref "CR3") (pin "1") (pinfunction "G_1") (pintype "passive"))
      (node (ref "CR4") (pin "1") (pinfunction "G_1") (pintype "passive"))
      (node (ref "CR5") (pin "1") (pinfunction "G_1") (pintype "passive"))
      (node (ref "CR6") (pin "1") (pinfunction "G_1") (pintype "passive"))
      (node (ref "CR7") (pin "1") (pinfunction "G_1") (pintype "passive"))
      (node (ref "CR8") (pin "1") (pinfunction "G_1") (pintype "passive"))
      (node (ref "CR9") (pin "1") (pinfunction "G_1") (pintype "passive"))
      (node (ref "J1") (pin "1") (pinfunction "1_1") (pintype "passive"))
      (node (ref "J1") (pin "3") (pinfunction "3_3") (pintype "passive"))
      (node (ref "J10") (pin "1") (pinfunction "1_1") (pintype "passive"))
      (node (ref "J10") (pin "3") (pinfunction "3_3") (pintype "passive"))
      (node (ref "J11") (pin "13") (pinfunction "13_13") (pintype "bidirectional"))
      (node (ref "J11") (pin "2") (pinfunction "2_2") (pintype "bidirectional"))
      (node (ref "J11") (pin "4") (pinfunction "4_4") (pintype "bidirectional"))
      (node (ref "J2") (pin "1") (pinfunction "1_1") (pintype "passive"))
      (node (ref "J2") (pin "3") (pinfunction "3_3") (pintype "passive"))
      (node (ref "J3") (pin "1") (pinfunction "1_1") (pintype "passive"))
      (node (ref "J3") (pin "3") (pinfunction "3_3") (pintype "passive"))
      (node (ref "J4") (pin "1") (pinfunction "1_1") (pintype "passive"))
      (node (ref "J4") (pin "3") (pinfunction "3_3") (pintype "passive"))
      (node (ref "J5") (pin "1") (pinfunction "1_1") (pintype "passive"))
      (node (ref "J5") (pin "3") (pinfunction "3_3") (pintype "passive"))
      (node (ref "J6") (pin "1") (pinfunction "1_1") (pintype "passive"))
      (node (ref "J6") (pin "3") (pinfunction "3_3") (pintype "passive"))
      (node (ref "J7") (pin "1") (pinfunction "1_1") (pintype "passive"))
      (node (ref "J7") (pin "3") (pinfunction "3_3") (pintype "passive"))
      (node (ref "J8") (pin "1") (pinfunction "1_1") (pintype "passive"))
      (node (ref "J8") (pin "3") (pinfunction "3_3") (pintype "passive"))
      (node (ref "J9") (pin "1") (pinfunction "1_1") (pintype "passive"))
      (node (ref "J9") (pin "3") (pinfunction "3_3") (pintype "passive"))
      (node (ref "PS1") (pin "2") (pinfunction "GND_2") (pintype "power_in"))
      (node (ref "R2") (pin "1") (pinfunction "1_1") (pintype "passive"))
      (node (ref "R22") (pin "1") (pinfunction "1_1") (pintype "passive"))
      (node (ref "R24") (pin "1") (pinfunction "1_1") (pintype "passive"))
      (node (ref "R26") (pin "1") (pinfunction "1_1") (pintype "passive"))
      (node (ref "R37") (pin "1") (pinfunction "1_1") (pintype "passive"))
      (node (ref "R39") (pin "1") (pinfunction "1_1") (pintype "passive"))
      (node (ref "R4") (pin "1") (pinfunction "1_1") (pintype "passive"))
      (node (ref "R41") (pin "1") (pinfunction "1_1") (pintype "passive"))
      (node (ref "R6") (pin "1") (pinfunction "1_1") (pintype "passive"))
      (node (ref "R8") (pin "1") (pinfunction "1_1") (pintype "passive"))
      (node (ref "RLA1") (pin "2") (pinfunction "GND_2") (pintype "passive"))
      (node (ref "U1") (pin "12") (pinfunction "P$V-_12") (pintype "bidirectional"))
      (node (ref "U2") (pin "10") (pinfunction "-IN_10") (pintype "input"))
      (node (ref "U2") (pin "11") (pinfunction "+IN_11") (pintype "input"))
      (node (ref "U2") (pin "12") (pinfunction "P$V-_12") (pintype "bidirectional"))
      (node (ref "U2") (pin "13") (pinfunction "OUT_13") (pintype "output"))
      (node (ref "U3") (pin "10") (pinfunction "-IN_10") (pintype "input"))
      (node (ref "U3") (pin "11") (pinfunction "+IN_11") (pintype "input"))
      (node (ref "U3") (pin "12") (pinfunction "P$V-_12") (pintype "bidirectional"))
      (node (ref "U3") (pin "13") (pinfunction "OUT_13") (pintype "output"))
    )
    (net (code "5") (name "Net-(LED1-C)") (class "Default")
      (node (ref "LED1") (pin "K") (pinfunction "C_K") (pintype "passive"))
      (node (ref "R13") (pin "1") (pinfunction "1_1") (pintype "passive"))
      (node (ref "U1") (pin "13") (pinfunction "OUT_13") (pintype "output"))
    )
    (net (code "6") (name "Net-(LED2-C)") (class "Default")
      (node (ref "LED2") (pin "K") (pinfunction "C_K") (pintype "passive"))
      (node (ref "R14") (pin "1") (pinfunction "1_1") (pintype "passive"))
      (node (ref "U1") (pin "14") (pinfunction "OUT_14") (pintype "output"))
    )
    (net (code "7") (name "Net-(LED3-C)") (class "Default")
      (node (ref "LED3") (pin "K") (pinfunction "C_K") (pintype "passive"))
      (node (ref "R15") (pin "1") (pinfunction "1_1") (pintype "passive"))
      (node (ref "U1") (pin "1") (pinfunction "OUT_1") (pintype "output"))
    )
    (net (code "8") (name "Net-(LED4-C)") (class "Default")
      (node (ref "LED4") (pin "K") (pinfunction "C_K") (pintype "passive"))
      (node (ref "R16") (pin "1") (pinfunction "1_1") (pintype "passive"))
      (node (ref "U1") (pin "2") (pinfunction "OUT_2") (pintype "output"))
    )
    (net (code "9") (name "Net-(LED5-C)") (class "Default")
      (node (ref "LED5") (pin "K") (pinfunction "C_K") (pintype "passive"))
      (node (ref "R30") (pin "1") (pinfunction "1_1") (pintype "passive"))
      (node (ref "U2") (pin "14") (pinfunction "OUT_14") (pintype "output"))
    )
    (net (code "10") (name "Net-(LED6-C)") (class "Default")
      (node (ref "LED6") (pin "K") (pinfunction "C_K") (pintype "passive"))
      (node (ref "R31") (pin "1") (pinfunction "1_1") (pintype "passive"))
      (node (ref "U2") (pin "1") (pinfunction "OUT_1") (pintype "output"))
    )
    (net (code "11") (name "Net-(LED7-C)") (class "Default")
      (node (ref "LED7") (pin "K") (pinfunction "C_K") (pintype "passive"))
      (node (ref "R32") (pin "1") (pinfunction "1_1") (pintype "passive"))
      (node (ref "U2") (pin "2") (pinfunction "OUT_2") (pintype "output"))
    )
    (net (code "12") (name "Net-(LED8-C)") (class "Default")
      (node (ref "LED8") (pin "K") (pinfunction "C_K") (pintype "passive"))
      (node (ref "R45") (pin "1") (pinfunction "1_1") (pintype "passive"))
      (node (ref "U3") (pin "14") (pinfunction "OUT_14") (pintype "output"))
    )
    (net (code "13") (name "Net-(LED9-C)") (class "Default")
      (node (ref "LED9") (pin "K") (pinfunction "C_K") (pintype "passive"))
      (node (ref "R46") (pin "1") (pinfunction "1_1") (pintype "passive"))
      (node (ref "U3") (pin "1") (pinfunction "OUT_1") (pintype "output"))
    )
    (net (code "14") (name "Net-(LED10-C)") (class "Default")
      (node (ref "LED10") (pin "K") (pinfunction "C_K") (pintype "passive"))
      (node (ref "R47") (pin "1") (pinfunction "1_1") (pintype "passive"))
      (node (ref "U3") (pin "2") (pinfunction "OUT_2") (pintype "output"))
    )
    (net (code "15") (name "REF1") (class "Default")
      (node (ref "R1") (pin "1") (pinfunction "1_1") (pintype "passive"))
      (node (ref "R13") (pin "2") (pinfunction "2_2") (pintype "passive"))
      (node (ref "R2") (pin "2") (pinfunction "2_2") (pintype "passive"))
      (node (ref "U1") (pin "11") (pinfunction "+IN_11") (pintype "input"))
    )
    (net (code "16") (name "REF2") (class "Default")
      (node (ref "R14") (pin "2") (pinfunction "2_2") (pintype "passive"))
      (node (ref "R3") (pin "1") (pinfunction "1_1") (pintype "passive"))
      (node (ref "R4") (pin "2") (pinfunction "2_2") (pintype "passive"))
      (node (ref "U1") (pin "9") (pinfunction "+IN_9") (pintype "input"))
    )
    (net (code "17") (name "REF3") (class "Default")
      (node (ref "R15") (pin "2") (pinfunction "2_2") (pintype "passive"))
      (node (ref "R5") (pin "1") (pinfunction "1_1") (pintype "passive"))
      (node (ref "R6") (pin "2") (pinfunction "2_2") (pintype "passive"))
      (node (ref "U1") (pin "7") (pinfunction "+IN_7") (pintype "input"))
    )
    (net (code "18") (name "REF4") (class "Default")
      (node (ref "R16") (pin "2") (pinfunction "2_2") (pintype "passive"))
      (node (ref "R7") (pin "1") (pinfunction "1_1") (pintype "passive"))
      (node (ref "R8") (pin "2") (pinfunction "2_2") (pintype "passive"))
      (node (ref "U1") (pin "5") (pinfunction "+IN_5") (pintype "input"))
    )
    (net (code "19") (name "REF5") (class "Default")
      (node (ref "R21") (pin "1") (pinfunction "1_1") (pintype "passive"))
      (node (ref "R22") (pin "2") (pinfunction "2_2") (pintype "passive"))
      (node (ref "R30") (pin "2") (pinfunction "2_2") (pintype "passive"))
      (node (ref "U2") (pin "9") (pinfunction "+IN_9") (pintype "input"))
    )
    (net (code "20") (name "REF6") (class "Default")
      (node (ref "R23") (pin "1") (pinfunction "1_1") (pintype "passive"))
      (node (ref "R24") (pin "2") (pinfunction "2_2") (pintype "passive"))
      (node (ref "R31") (pin "2") (pinfunction "2_2") (pintype "passive"))
      (node (ref "U2") (pin "7") (pinfunction "+IN_7") (pintype "input"))
    )
    (net (code "21") (name "REF7") (class "Default")
      (node (ref "R25") (pin "1") (pinfunction "1_1") (pintype "passive"))
      (node (ref "R26") (pin "2") (pinfunction "2_2") (pintype "passive"))
      (node (ref "R32") (pin "2") (pinfunction "2_2") (pintype "passive"))
      (node (ref "U2") (pin "5") (pinfunction "+IN_5") (pintype "input"))
    )
    (net (code "22") (name "REF8") (class "Default")
      (node (ref "R36") (pin "1") (pinfunction "1_1") (pintype "passive"))
      (node (ref "R37") (pin "2") (pinfunction "2_2") (pintype "passive"))
      (node (ref "R45") (pin "2") (pinfunction "2_2") (pintype "passive"))
      (node (ref "U3") (pin "9") (pinfunction "+IN_9") (pintype "input"))
    )
    (net (code "23") (name "REF9") (class "Default")
      (node (ref "R38") (pin "1") (pinfunction "1_1") (pintype "passive"))
      (node (ref "R39") (pin "2") (pinfunction "2_2") (pintype "passive"))
      (node (ref "R46") (pin "2") (pinfunction "2_2") (pintype "passive"))
      (node (ref "U3") (pin "7") (pinfunction "+IN_7") (pintype "input"))
    )
    (net (code "24") (name "REF10") (class "Default")
      (node (ref "R40") (pin "1") (pinfunction "1_1") (pintype "passive"))
      (node (ref "R41") (pin "2") (pinfunction "2_2") (pintype "passive"))
      (node (ref "R47") (pin "2") (pinfunction "2_2") (pintype "passive"))
      (node (ref "U3") (pin "5") (pinfunction "+IN_5") (pintype "input"))
    )
    (net (code "25") (name "THER1-IN") (class "Default")
      (node (ref "CR1") (pin "3") (pinfunction "3_3") (pintype "passive"))
      (node (ref "J1") (pin "4") (pinfunction "4_4") (pintype "passive"))
      (node (ref "R9") (pin "1") (pinfunction "1_1") (pintype "passive"))
      (node (ref "U1") (pin "10") (pinfunction "-IN_10") (pintype "input"))
    )
    (net (code "26") (name "THER1-SIG") (class "Default")
      (node (ref "J11") (pin "15") (pinfunction "15_15") (pintype "bidirectional"))
      (node (ref "LED1") (pin "A") (pinfunction "A_A") (pintype "passive"))
    )
    (net (code "27") (name "THER2-IN") (class "Default")
      (node (ref "CR2") (pin "3") (pinfunction "3_3") (pintype "passive"))
      (node (ref "J2") (pin "4") (pinfunction "4_4") (pintype "passive"))
      (node (ref "R10") (pin "1") (pinfunction "1_1") (pintype "passive"))
      (node (ref "U1") (pin "8") (pinfunction "-IN_8") (pintype "input"))
    )
    (net (code "28") (name "THER2-SIG") (class "Default")
      (node (ref "J11") (pin "12") (pinfunction "12_12") (pintype "bidirectional"))
      (node (ref "LED2") (pin "A") (pinfunction "A_A") (pintype "passive"))
    )
    (net (code "29") (name "THER3-IN") (class "Default")
      (node (ref "CR3") (pin "3") (pinfunction "3_3") (pintype "passive"))
      (node (ref "J3") (pin "4") (pinfunction "4_4") (pintype "passive"))
      (node (ref "R11") (pin "1") (pinfunction "1_1") (pintype "passive"))
      (node (ref "U1") (pin "6") (pinfunction "-IN_6") (pintype "input"))
    )
    (net (code "30") (name "THER3-SIG") (class "Default")
      (node (ref "J11") (pin "11") (pinfunction "11_11") (pintype "bidirectional"))
      (node (ref "LED3") (pin "A") (pinfunction "A_A") (pintype "passive"))
    )
    (net (code "31") (name "THER4-IN") (class "Default")
      (node (ref "CR4") (pin "3") (pinfunction "3_3") (pintype "passive"))
      (node (ref "J4") (pin "4") (pinfunction "4_4") (pintype "passive"))
      (node (ref "R12") (pin "1") (pinfunction "1_1") (pintype "passive"))
      (node (ref "U1") (pin "4") (pinfunction "-IN_4") (pintype "input"))
    )
    (net (code "32") (name "THER4-SIG") (class "Default")
      (node (ref "J11") (pin "16") (pinfunction "16_16") (pintype "bidirectional"))
      (node (ref "LED4") (pin "A") (pinfunction "A_A") (pintype "passive"))
    )
    (net (code "33") (name "THER5-IN") (class "Default")
      (node (ref "CR5") (pin "3") (pinfunction "3_3") (pintype "passive"))
      (node (ref "J5") (pin "4") (pinfunction "4_4") (pintype "passive"))
      (node (ref "R27") (pin "1") (pinfunction "1_1") (pintype "passive"))
      (node (ref "U2") (pin "8") (pinfunction "-IN_8") (pintype "input"))
    )
    (net (code "34") (name "THER5-SIG") (class "Default")
      (node (ref "J11") (pin "8") (pinfunction "8_8") (pintype "bidirectional"))
      (node (ref "LED5") (pin "A") (pinfunction "A_A") (pintype "passive"))
    )
    (net (code "35") (name "THER6-IN") (class "Default")
      (node (ref "CR6") (pin "3") (pinfunction "3_3") (pintype "passive"))
      (node (ref "J6") (pin "4") (pinfunction "4_4") (pintype "passive"))
      (node (ref "R28") (pin "1") (pinfunction "1_1") (pintype "passive"))
      (node (ref "U2") (pin "6") (pinfunction "-IN_6") (pintype "input"))
    )
    (net (code "36") (name "THER6-SIG") (class "Default")
      (node (ref "J11") (pin "10") (pinfunction "10_10") (pintype "bidirectional"))
      (node (ref "LED6") (pin "A") (pinfunction "A_A") (pintype "passive"))
    )
    (net (code "37") (name "THER7-IN") (class "Default")
      (node (ref "CR7") (pin "3") (pinfunction "3_3") (pintype "passive"))
      (node (ref "J7") (pin "4") (pinfunction "4_4") (pintype "passive"))
      (node (ref "R29") (pin "1") (pinfunction "1_1") (pintype "passive"))
      (node (ref "U2") (pin "4") (pinfunction "-IN_4") (pintype "input"))
    )
    (net (code "38") (name "THER7-SIG") (class "Default")
      (node (ref "J11") (pin "9") (pinfunction "9_9") (pintype "bidirectional"))
      (node (ref "LED7") (pin "A") (pinfunction "A_A") (pintype "passive"))
    )
    (net (code "39") (name "THER8-IN") (class "Default")
      (node (ref "CR8") (pin "3") (pinfunction "3_3") (pintype "passive"))
      (node (ref "J8") (pin "4") (pinfunction "4_4") (pintype "passive"))
      (node (ref "R42") (pin "1") (pinfunction "1_1") (pintype "passive"))
      (node (ref "U3") (pin "8") (pinfunction "-IN_8") (pintype "input"))
    )
    (net (code "40") (name "THER8-SIG") (class "Default")
      (node (ref "J11") (pin "6") (pinfunction "6_6") (pintype "bidirectional"))
      (node (ref "LED8") (pin "A") (pinfunction "A_A") (pintype "passive"))
    )
    (net (code "41") (name "THER9-IN") (class "Default")
      (node (ref "CR9") (pin "3") (pinfunction "3_3") (pintype "passive"))
      (node (ref "J9") (pin "4") (pinfunction "4_4") (pintype "passive"))
      (node (ref "R43") (pin "1") (pinfunction "1_1") (pintype "passive"))
      (node (ref "U3") (pin "6") (pinfunction "-IN_6") (pintype "input"))
    )
    (net (code "42") (name "THER9-SIG") (class "Default")
      (node (ref "J11") (pin "7") (pinfunction "7_7") (pintype "bidirectional"))
      (node (ref "LED9") (pin "A") (pinfunction "A_A") (pintype "passive"))
    )
    (net (code "43") (name "THER10-IN") (class "Default")
      (node (ref "CR10") (pin "3") (pinfunction "3_3") (pintype "passive"))
      (node (ref "J10") (pin "4") (pinfunction "4_4") (pintype "passive"))
      (node (ref "R44") (pin "1") (pinfunction "1_1") (pintype "passive"))
      (node (ref "U3") (pin "4") (pinfunction "-IN_4") (pintype "input"))
    )
    (net (code "44") (name "THER10-SIG") (class "Default")
      (node (ref "J11") (pin "5") (pinfunction "5_5") (pintype "bidirectional"))
      (node (ref "LED10") (pin "A") (pinfunction "A_A") (pintype "passive"))
    )
    (net (code "45") (name "unconnected-(CR1-NC-Pad2)") (class "Default")
      (node (ref "CR1") (pin "2") (pinfunction "NC_2") (pintype "no_connect"))
    )
    (net (code "46") (name "unconnected-(CR2-NC-Pad2)") (class "Default")
      (node (ref "CR2") (pin "2") (pinfunction "NC_2") (pintype "no_connect"))
    )
    (net (code "47") (name "unconnected-(CR3-NC-Pad2)") (class "Default")
      (node (ref "CR3") (pin "2") (pinfunction "NC_2") (pintype "no_connect"))
    )
    (net (code "48") (name "unconnected-(CR4-NC-Pad2)") (class "Default")
      (node (ref "CR4") (pin "2") (pinfunction "NC_2") (pintype "no_connect"))
    )
    (net (code "49") (name "unconnected-(CR5-NC-Pad2)") (class "Default")
      (node (ref "CR5") (pin "2") (pinfunction "NC_2") (pintype "no_connect"))
    )
    (net (code "50") (name "unconnected-(CR6-NC-Pad2)") (class "Default")
      (node (ref "CR6") (pin "2") (pinfunction "NC_2") (pintype "no_connect"))
    )
    (net (code "51") (name "unconnected-(CR7-NC-Pad2)") (class "Default")
      (node (ref "CR7") (pin "2") (pinfunction "NC_2") (pintype "no_connect"))
    )
    (net (code "52") (name "unconnected-(CR8-NC-Pad2)") (class "Default")
      (node (ref "CR8") (pin "2") (pinfunction "NC_2") (pintype "no_connect"))
    )
    (net (code "53") (name "unconnected-(CR9-NC-Pad2)") (class "Default")
      (node (ref "CR9") (pin "2") (pinfunction "NC_2") (pintype "no_connect"))
    )
    (net (code "54") (name "unconnected-(CR10-NC-Pad2)") (class "Default")
      (node (ref "CR10") (pin "2") (pinfunction "NC_2") (pintype "no_connect"))
    )
    (net (code "55") (name "unconnected-(J1-SHIELD-PadS1)") (class "Default")
      (node (ref "J1") (pin "S1") (pinfunction "SHIELD_S1") (pintype "passive"))
    )
    (net (code "56") (name "unconnected-(J2-SHIELD-PadS1)") (class "Default")
      (node (ref "J2") (pin "S1") (pinfunction "SHIELD_S1") (pintype "passive"))
    )
    (net (code "57") (name "unconnected-(J3-SHIELD-PadS1)") (class "Default")
      (node (ref "J3") (pin "S1") (pinfunction "SHIELD_S1") (pintype "passive"))
    )
    (net (code "58") (name "unconnected-(J4-SHIELD-PadS1)") (class "Default")
      (node (ref "J4") (pin "S1") (pinfunction "SHIELD_S1") (pintype "passive"))
    )
    (net (code "59") (name "unconnected-(J5-SHIELD-PadS1)") (class "Default")
      (node (ref "J5") (pin "S1") (pinfunction "SHIELD_S1") (pintype "passive"))
    )
    (net (code "60") (name "unconnected-(J6-SHIELD-PadS1)") (class "Default")
      (node (ref "J6") (pin "S1") (pinfunction "SHIELD_S1") (pintype "passive"))
    )
    (net (code "61") (name "unconnected-(J7-SHIELD-PadS1)") (class "Default")
      (node (ref "J7") (pin "S1") (pinfunction "SHIELD_S1") (pintype "passive"))
    )
    (net (code "62") (name "unconnected-(J8-SHIELD-PadS1)") (class "Default")
      (node (ref "J8") (pin "S1") (pinfunction "SHIELD_S1") (pintype "passive"))
    )
    (net (code "63") (name "unconnected-(J9-SHIELD-PadS1)") (class "Default")
      (node (ref "J9") (pin "S1") (pinfunction "SHIELD_S1") (pintype "passive"))
    )
    (net (code "64") (name "unconnected-(J10-SHIELD-PadS1)") (class "Default")
      (node (ref "J10") (pin "S1") (pinfunction "SHIELD_S1") (pintype "passive"))
    )
  )
)
